# LithiumBatteryPack.net
KiCad netlist of a schematic drawn in Altium Designer
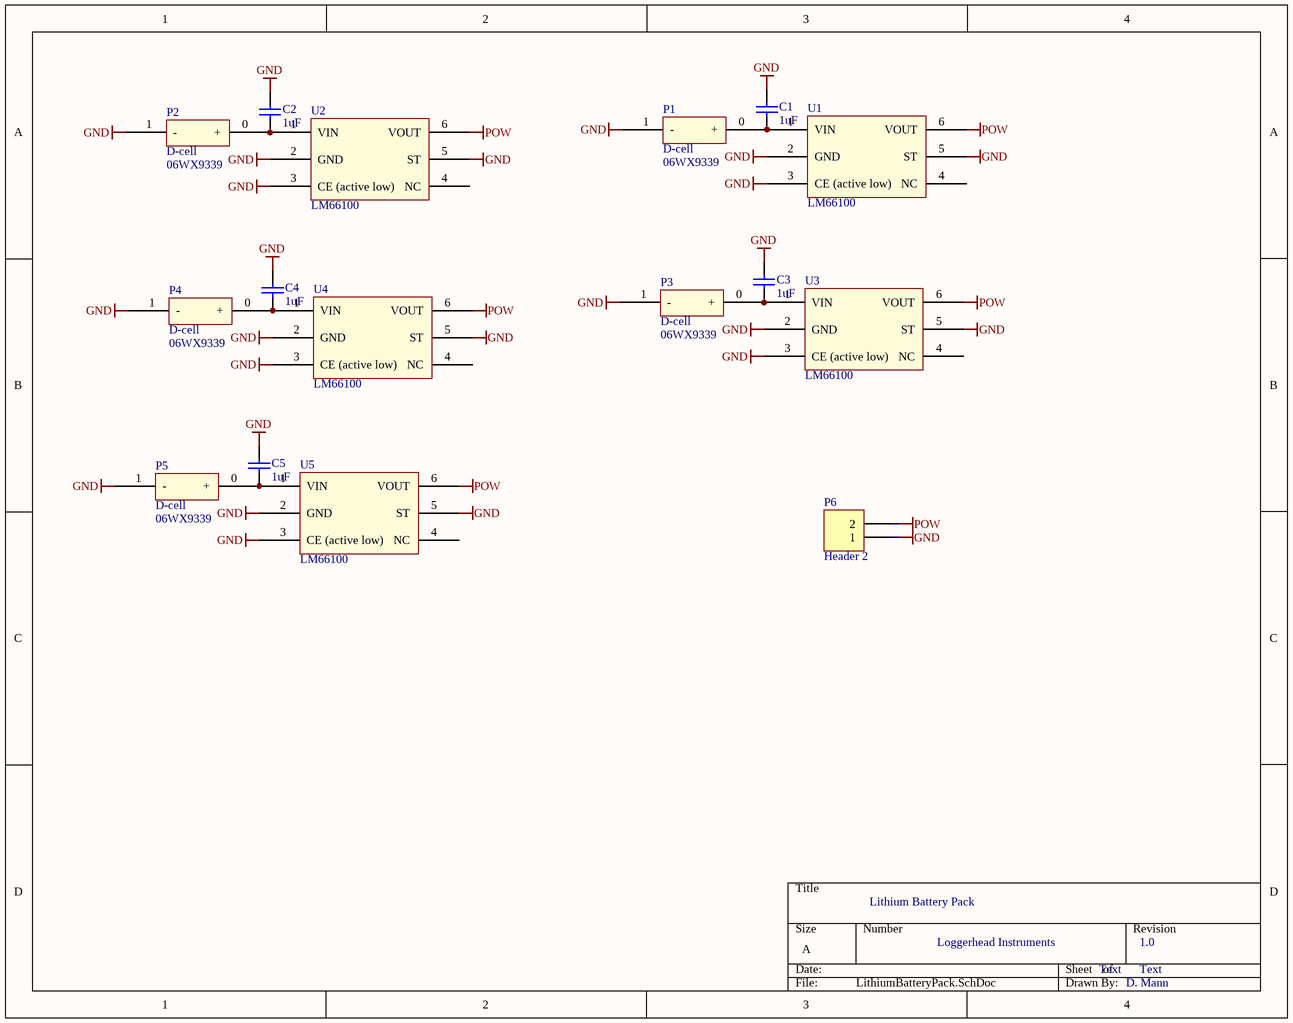
[diagram p0: LithiumBatteryPack.SchDoc]

(export (version "E")
  (design (tool "Eeschema 10.0.6"))
  (components
    (comp (ref "C1")
      (value "1uF")
      (footprint "0402")
      (description "Ceramic Chip Capacitor - Standard")
      (fields (field (name "PUBLISHER") "Altium Limited"))
      (libsource (lib "KEMET Chip Capacitor") (part "C0402"))
    )
    (comp (ref "C2")
      (value "1uF")
      (footprint "0402")
      (description "Ceramic Chip Capacitor - Standard")
      (fields (field (name "PUBLISHER") "Altium Limited"))
      (libsource (lib "KEMET Chip Capacitor") (part "C0402"))
    )
    (comp (ref "C3")
      (value "1uF")
      (footprint "0402")
      (description "Ceramic Chip Capacitor - Standard")
      (fields (field (name "PUBLISHER") "Altium Limited"))
      (libsource (lib "KEMET Chip Capacitor") (part "C0402"))
    )
    (comp (ref "C4")
      (value "1uF")
      (footprint "0402")
      (description "Ceramic Chip Capacitor - Standard")
      (fields (field (name "PUBLISHER") "Altium Limited"))
      (libsource (lib "KEMET Chip Capacitor") (part "C0402"))
    )
    (comp (ref "C5")
      (value "1uF")
      (footprint "0402")
      (description "Ceramic Chip Capacitor - Standard")
      (fields (field (name "PUBLISHER") "Altium Limited"))
      (libsource (lib "KEMET Chip Capacitor") (part "C0402"))
    )
    (comp (ref "P1")
      (value "D-cell")
      (footprint "Battery-D")
      (fields (field (name "SUPPLIER PART NUMBER 1") "06WX9339"))
      (libsource (lib "Loggerhead") (part "Battery-D"))
    )
    (comp (ref "P2")
      (value "D-cell")
      (footprint "Battery-D")
      (fields (field (name "SUPPLIER PART NUMBER 1") "06WX9339"))
      (libsource (lib "Loggerhead") (part "Battery-D"))
    )
    (comp (ref "P3")
      (value "D-cell")
      (footprint "Battery-D")
      (fields (field (name "SUPPLIER PART NUMBER 1") "06WX9339"))
      (libsource (lib "Loggerhead") (part "Battery-D"))
    )
    (comp (ref "P4")
      (value "D-cell")
      (footprint "Battery-D")
      (fields (field (name "SUPPLIER PART NUMBER 1") "06WX9339"))
      (libsource (lib "Loggerhead") (part "Battery-D"))
    )
    (comp (ref "P5")
      (value "D-cell")
      (footprint "Battery-D")
      (fields (field (name "SUPPLIER PART NUMBER 1") "06WX9339"))
      (libsource (lib "Loggerhead") (part "Battery-D"))
    )
    (comp (ref "P6")
      (value "Header 2")
      (footprint "HDR1X2")
      (description "Header, 2-Pin")
      (fields (field (name "PUBLISHER") "Altium Limited"))
      (libsource (lib "Miscellaneous Connectors") (part "Header 2"))
    )
    (comp (ref "U1") (value "LM66100") (footprint "SC-70-6") (libsource (lib "Loggerhead") (part "LM66100")))
    (comp (ref "U2") (value "LM66100") (footprint "SC-70-6") (libsource (lib "Loggerhead") (part "LM66100")))
    (comp (ref "U3") (value "LM66100") (footprint "SC-70-6") (libsource (lib "Loggerhead") (part "LM66100")))
    (comp (ref "U4") (value "LM66100") (footprint "SC-70-6") (libsource (lib "Loggerhead") (part "LM66100")))
    (comp (ref "U5") (value "LM66100") (footprint "SC-70-6") (libsource (lib "Loggerhead") (part "LM66100")))
  )
  (nets
    (net (code "1") (name "GND") (class "Default")
      (node (ref "C1") (pin "1") (pinfunction "1_1") (pintype "passive"))
      (node (ref "C2") (pin "1") (pinfunction "1_1") (pintype "passive"))
      (node (ref "C3") (pin "1") (pinfunction "1_1") (pintype "passive"))
      (node (ref "C4") (pin "1") (pinfunction "1_1") (pintype "passive"))
      (node (ref "C5") (pin "1") (pinfunction "1_1") (pintype "passive"))
      (node (ref "P1") (pin "1") (pinfunction "-_1") (pintype "passive"))
      (node (ref "P2") (pin "1") (pinfunction "-_1") (pintype "passive"))
      (node (ref "P3") (pin "1") (pinfunction "-_1") (pintype "passive"))
      (node (ref "P4") (pin "1") (pinfunction "-_1") (pintype "passive"))
      (node (ref "P5") (pin "1") (pinfunction "-_1") (pintype "passive"))
      (node (ref "P6") (pin "1") (pinfunction "1_1") (pintype "passive"))
      (node (ref "U1") (pin "2") (pinfunction "GND_2") (pintype "passive"))
      (node (ref "U1") (pin "3") (pinfunction "CE_(active_low)_3") (pintype "passive"))
      (node (ref "U1") (pin "5") (pinfunction "ST_5") (pintype "passive"))
      (node (ref "U2") (pin "2") (pinfunction "GND_2") (pintype "passive"))
      (node (ref "U2") (pin "3") (pinfunction "CE_(active_low)_3") (pintype "passive"))
      (node (ref "U2") (pin "5") (pinfunction "ST_5") (pintype "passive"))
      (node (ref "U3") (pin "2") (pinfunction "GND_2") (pintype "passive"))
      (node (ref "U3") (pin "3") (pinfunction "CE_(active_low)_3") (pintype "passive"))
      (node (ref "U3") (pin "5") (pinfunction "ST_5") (pintype "passive"))
      (node (ref "U4") (pin "2") (pinfunction "GND_2") (pintype "passive"))
      (node (ref "U4") (pin "3") (pinfunction "CE_(active_low)_3") (pintype "passive"))
      (node (ref "U4") (pin "5") (pinfunction "ST_5") (pintype "passive"))
      (node (ref "U5") (pin "2") (pinfunction "GND_2") (pintype "passive"))
      (node (ref "U5") (pin "3") (pinfunction "CE_(active_low)_3") (pintype "passive"))
      (node (ref "U5") (pin "5") (pinfunction "ST_5") (pintype "passive"))
    )
    (net (code "2") (name "Net-(P1-+)") (class "Default")
      (node (ref "C1") (pin "2") (pinfunction "2_2") (pintype "passive"))
      (node (ref "P1") (pin "0") (pinfunction "+_0") (pintype "passive"))
      (node (ref "U1") (pin "1") (pinfunction "VIN_1") (pintype "passive"))
    )
    (net (code "3") (name "Net-(P2-+)") (class "Default")
      (node (ref "C2") (pin "2") (pinfunction "2_2") (pintype "passive"))
      (node (ref "P2") (pin "0") (pinfunction "+_0") (pintype "passive"))
      (node (ref "U2") (pin "1") (pinfunction "VIN_1") (pintype "passive"))
    )
    (net (code "4") (name "Net-(P3-+)") (class "Default")
      (node (ref "C3") (pin "2") (pinfunction "2_2") (pintype "passive"))
      (node (ref "P3") (pin "0") (pinfunction "+_0") (pintype "passive"))
      (node (ref "U3") (pin "1") (pinfunction "VIN_1") (pintype "passive"))
    )
    (net (code "5") (name "Net-(P4-+)") (class "Default")
      (node (ref "C4") (pin "2") (pinfunction "2_2") (pintype "passive"))
      (node (ref "P4") (pin "0") (pinfunction "+_0") (pintype "passive"))
      (node (ref "U4") (pin "1") (pinfunction "VIN_1") (pintype "passive"))
    )
    (net (code "6") (name "Net-(P5-+)") (class "Default")
      (node (ref "C5") (pin "2") (pinfunction "2_2") (pintype "passive"))
      (node (ref "P5") (pin "0") (pinfunction "+_0") (pintype "passive"))
      (node (ref "U5") (pin "1") (pinfunction "VIN_1") (pintype "passive"))
    )
    (net (code "7") (name "POW") (class "Default")
      (node (ref "P6") (pin "2") (pinfunction "2_2") (pintype "passive"))
      (node (ref "U1") (pin "6") (pinfunction "VOUT_6") (pintype "passive"))
      (node (ref "U2") (pin "6") (pinfunction "VOUT_6") (pintype "passive"))
      (node (ref "U3") (pin "6") (pinfunction "VOUT_6") (pintype "passive"))
      (node (ref "U4") (pin "6") (pinfunction "VOUT_6") (pintype "passive"))
      (node (ref "U5") (pin "6") (pinfunction "VOUT_6") (pintype "passive"))
    )
    (net (code "8") (name "unconnected-(U1-NC-Pad4)") (class "Default")
      (node (ref "U1") (pin "4") (pinfunction "NC_4") (pintype "passive"))
    )
    (net (code "9") (name "unconnected-(U2-NC-Pad4)") (class "Default")
      (node (ref "U2") (pin "4") (pinfunction "NC_4") (pintype "passive"))
    )
    (net (code "10") (name "unconnected-(U3-NC-Pad4)") (class "Default")
      (node (ref "U3") (pin "4") (pinfunction "NC_4") (pintype "passive"))
    )
    (net (code "11") (name "unconnected-(U4-NC-Pad4)") (class "Default")
      (node (ref "U4") (pin "4") (pinfunction "NC_4") (pintype "passive"))
    )
    (net (code "12") (name "unconnected-(U5-NC-Pad4)") (class "Default")
      (node (ref "U5") (pin "4") (pinfunction "NC_4") (pintype "passive"))
    )
  )
)
